# PROB_S7CAS_Connectors.net
KiCad netlist of a schematic drawn in Altium Designer
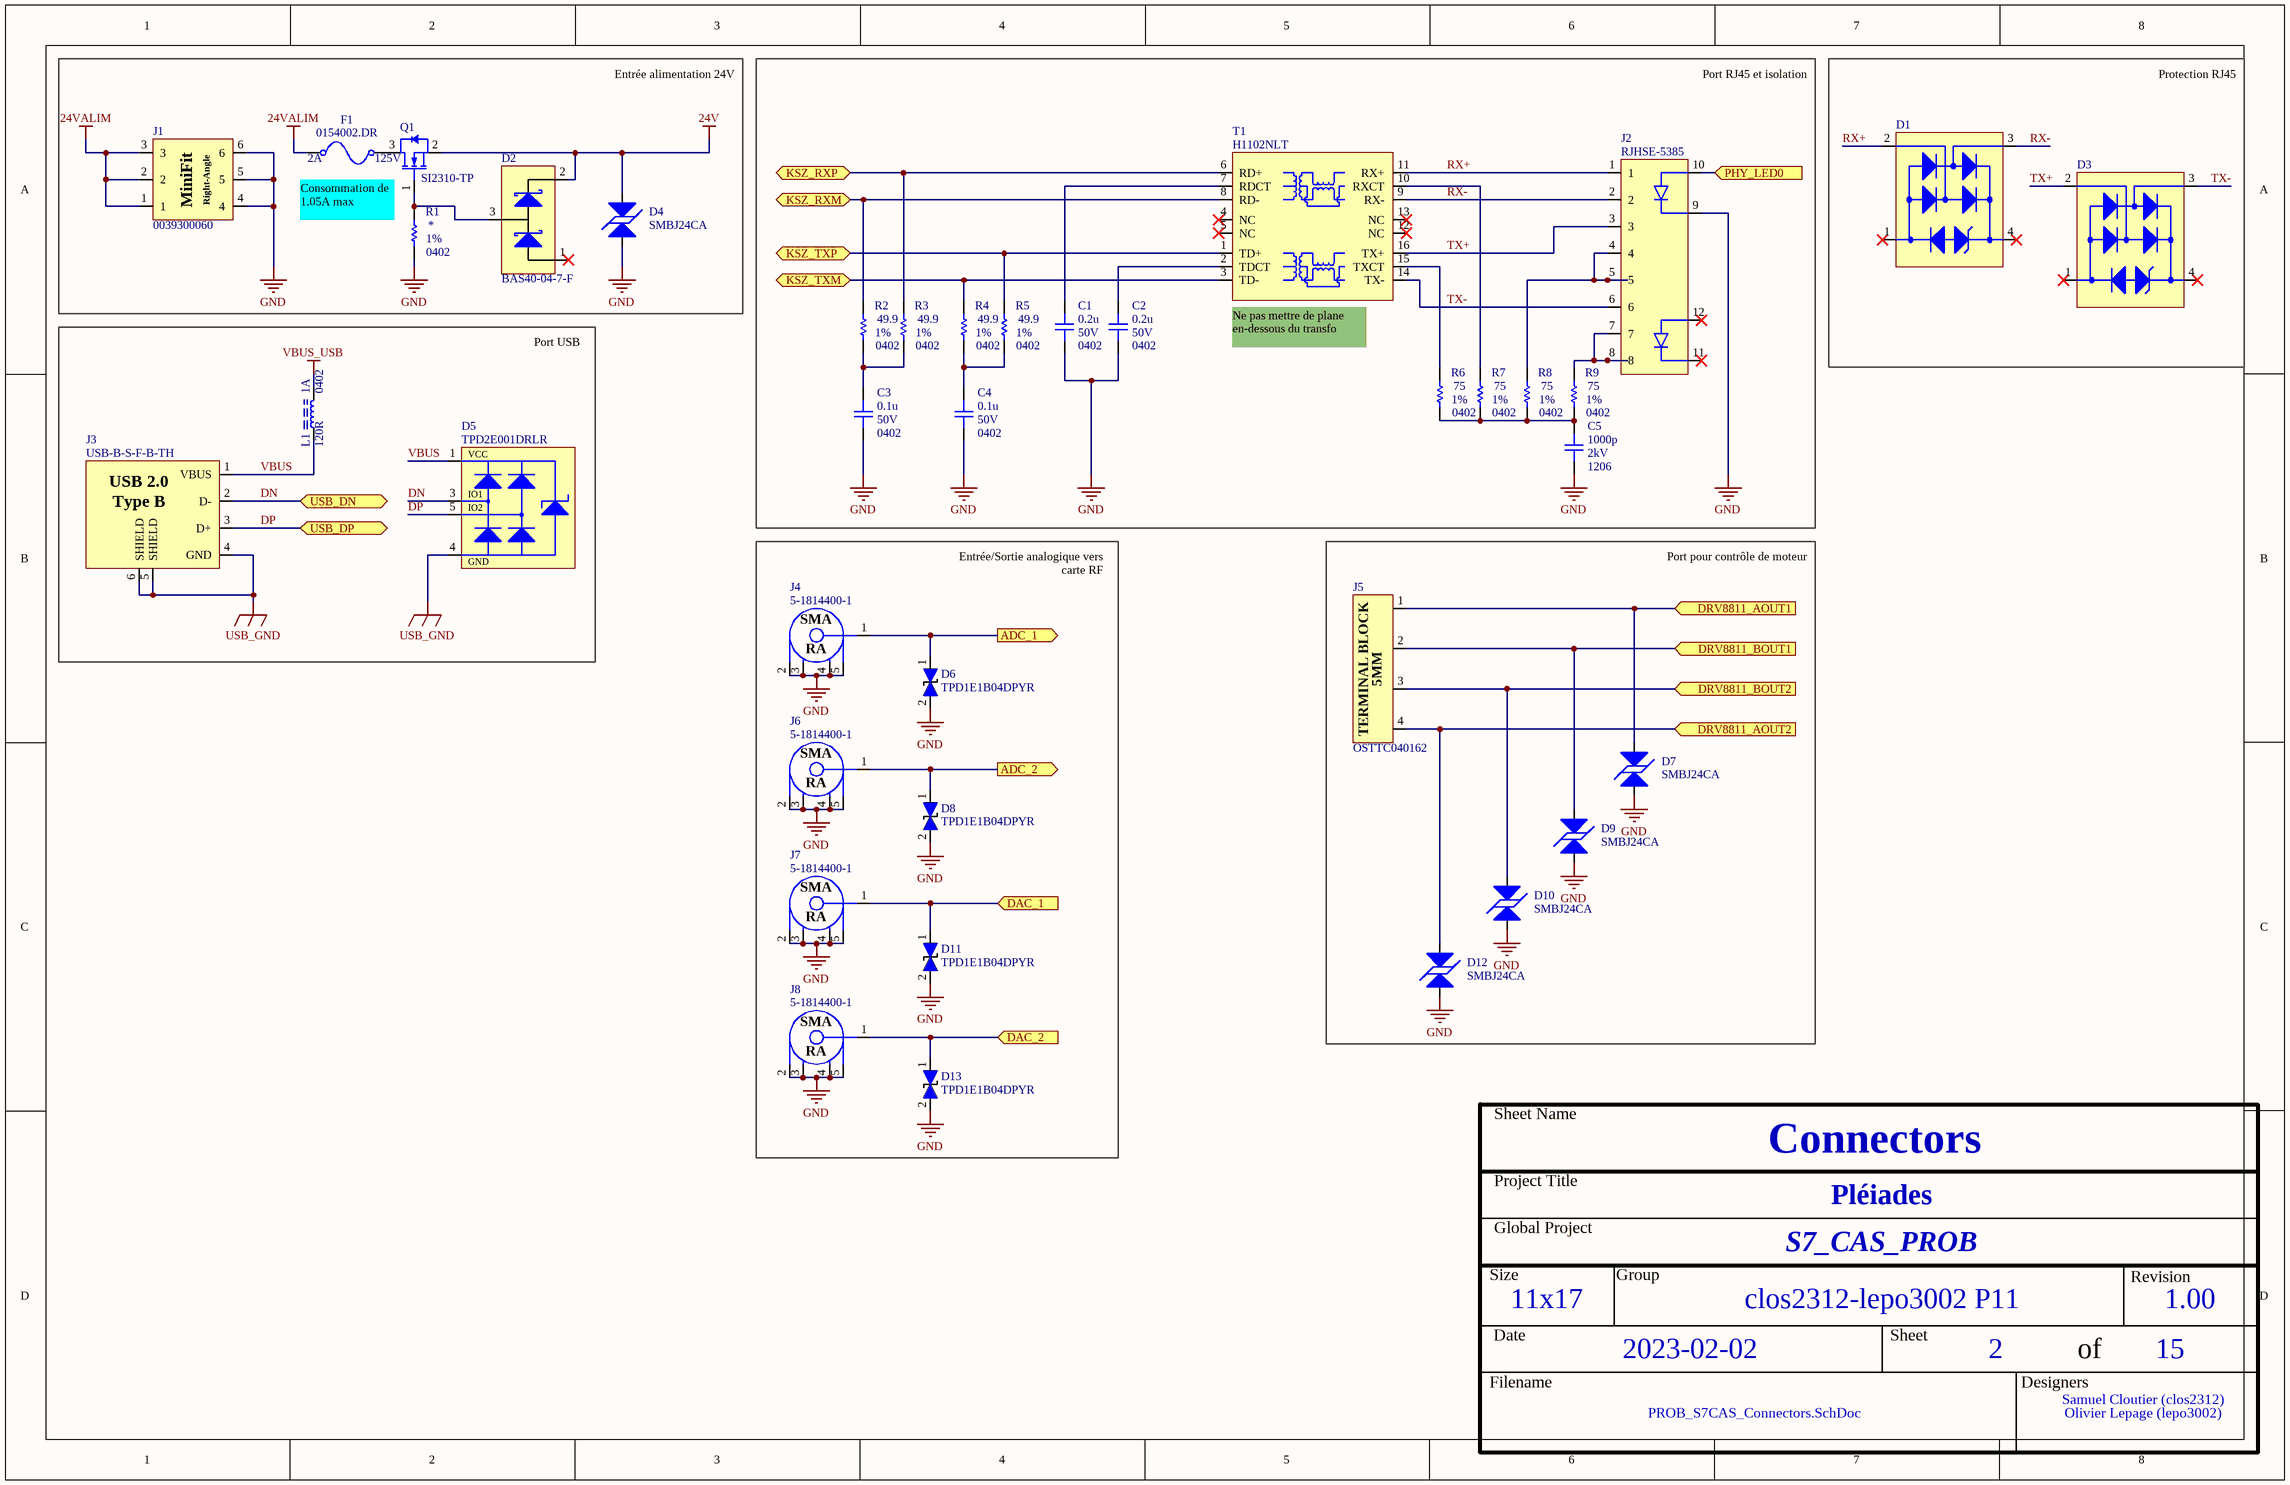
[diagram p0: PROB_S7CAS_Connectors.SchDoc]

(export (version "E")
  (design (tool "Eeschema 10.0.6"))
  (components
    (comp (ref "C1")
      (value "0.2u")
      (footprint "CAP_0402")
      (description "CAP - 0402")
      (fields
        (field (name "VOLTAGE") "50V")
        (field (name "PACKAGE") "0402")
        (field (name "CREATEDBY") "Jonathan Bouchard")
      )
      (libsource (lib "S7CAS_LIB2021") (part "CAP - 0402"))
    )
    (comp (ref "C2")
      (value "0.2u")
      (footprint "CAP_0402")
      (description "CAP - 0402")
      (fields
        (field (name "VOLTAGE") "50V")
        (field (name "PACKAGE") "0402")
        (field (name "CREATEDBY") "Jonathan Bouchard")
      )
      (libsource (lib "S7CAS_LIB2021") (part "CAP - 0402"))
    )
    (comp (ref "C3")
      (value "0.1u")
      (footprint "CAP_0402")
      (description "CAP - 0402")
      (fields
        (field (name "VOLTAGE") "50V")
        (field (name "PACKAGE") "0402")
        (field (name "CREATEDBY") "Jonathan Bouchard")
      )
      (libsource (lib "S7CAS_LIB2021") (part "CAP - 0402"))
    )
    (comp (ref "C4")
      (value "0.1u")
      (footprint "CAP_0402")
      (description "CAP - 0402")
      (fields
        (field (name "VOLTAGE") "50V")
        (field (name "PACKAGE") "0402")
        (field (name "CREATEDBY") "Jonathan Bouchard")
      )
      (libsource (lib "S7CAS_LIB2021") (part "CAP - 0402"))
    )
    (comp (ref "C5")
      (value "1000p")
      (footprint "CAP_0402")
      (description "CAP - 0402")
      (fields
        (field (name "VOLTAGE") "2kV")
        (field (name "PACKAGE") "1206")
        (field (name "CREATEDBY") "Jonathan Bouchard")
      )
      (libsource (lib "S7CAS_LIB2021") (part "CAP - 0402"))
    )
    (comp (ref "D1")
      (value "SR3.3.TCT")
      (footprint "TVS_SR3.3.TCT")
      (description "TVS - DIODE ARRAY 3.3V 150W - SOT143-4")
      (fields
        (field (name "MFG") "Semtech")
        (field (name "POWER") "150W")
        (field (name "CREATEDBY") "Jonathan Bouchard")
      )
      (libsource (lib "S7CAS_LIB2021") (part "TVS_SR3.3.TCT"))
    )
    (comp (ref "D2")
      (value "BAS40-04-7-F")
      (footprint "DIO_SCHOTTKY_BAS40-04-7-F")
      (description "DIO - Schottky Array 1 Pair Series Connection - SOT-23-3")
      (fields
        (field (name "CREATEDBY/DATE") "Danae D-F 15 août 2019")
        (field (name "VERIFIEDBY") "C.Paulin - 16/08/2019")
      )
      (libsource (lib "S7CAS_LIB2021") (part "DIO_SCHOTTKY_BAS40-04-7-F"))
    )
    (comp (ref "D3")
      (value "SR3.3.TCT")
      (footprint "TVS_SR3.3.TCT")
      (description "TVS - DIODE ARRAY 3.3V 150W - SOT143-4")
      (fields
        (field (name "MFG") "Semtech")
        (field (name "POWER") "150W")
        (field (name "CREATEDBY") "Jonathan Bouchard")
      )
      (libsource (lib "S7CAS_LIB2021") (part "TVS_SR3.3.TCT"))
    )
    (comp (ref "D4")
      (value "SMBJ24CA")
      (footprint "TVS_PWR_SMBJ36CA")
      (description "TVS - 24V 26.7V 600W - DO214AA")
      (fields
        (field (name "CREATEDBY/DATE") "Arnaud Samson - 06/07/18")
        (field (name "VERIFIEDBY") "Jonathan Bouchard - 2018-07-13")
      )
      (libsource (lib "S7CAS_LIB2021") (part "TVS_PWR_SMBJ24CA"))
    )
    (comp (ref "D5")
      (value "TPD2E001DRLR")
      (footprint "TVS_USB_TPD2E001DRLR")
      (description "TVS - USB TVS DIODE 5.5V - SOT-553")
      (fields
        (field (name "CREATEDBY/DATE") "Jonathan Bouchard 2018-07-10")
        (field (name "VERIFIEDBY") "Arnaud Samson 16-07-18")
      )
      (libsource (lib "S7CAS_LIB2021") (part "TVS_USB_TPD2E001DRLR"))
    )
    (comp (ref "D6")
      (value "TPD1E1B04DPYR")
      (footprint "TVS_DATA_TPD1E1B04DPYR")
      (description "TVS - TVS DIODE 3.6V 8.5V - 0402")
      (fields
        (field (name "CREATEDBY/DATE") "Keven Deslandes - 2018/10/19")
        (field (name "VERIFIEDBY") "Caroline Paulin - 28 janv 2019")
      )
      (libsource (lib "S7CAS_LIB2021") (part "TVS_DATA_TPD1E1B04DPYR"))
    )
    (comp (ref "D7")
      (value "SMBJ24CA")
      (footprint "TVS_PWR_SMBJ36CA")
      (description "TVS - 24V 26.7V 600W - DO214AA")
      (fields
        (field (name "CREATEDBY/DATE") "Arnaud Samson - 06/07/18")
        (field (name "VERIFIEDBY") "Jonathan Bouchard - 2018-07-13")
      )
      (libsource (lib "S7CAS_LIB2021") (part "TVS_PWR_SMBJ24CA"))
    )
    (comp (ref "D8")
      (value "TPD1E1B04DPYR")
      (footprint "TVS_DATA_TPD1E1B04DPYR")
      (description "TVS - TVS DIODE 3.6V 8.5V - 0402")
      (fields
        (field (name "CREATEDBY/DATE") "Keven Deslandes - 2018/10/19")
        (field (name "VERIFIEDBY") "Caroline Paulin - 28 janv 2019")
      )
      (libsource (lib "S7CAS_LIB2021") (part "TVS_DATA_TPD1E1B04DPYR"))
    )
    (comp (ref "D9")
      (value "SMBJ24CA")
      (footprint "TVS_PWR_SMBJ36CA")
      (description "TVS - 24V 26.7V 600W - DO214AA")
      (fields
        (field (name "CREATEDBY/DATE") "Arnaud Samson - 06/07/18")
        (field (name "VERIFIEDBY") "Jonathan Bouchard - 2018-07-13")
      )
      (libsource (lib "S7CAS_LIB2021") (part "TVS_PWR_SMBJ24CA"))
    )
    (comp (ref "D10")
      (value "SMBJ24CA")
      (footprint "TVS_PWR_SMBJ36CA")
      (description "TVS - 24V 26.7V 600W - DO214AA")
      (fields
        (field (name "CREATEDBY/DATE") "Arnaud Samson - 06/07/18")
        (field (name "VERIFIEDBY") "Jonathan Bouchard - 2018-07-13")
      )
      (libsource (lib "S7CAS_LIB2021") (part "TVS_PWR_SMBJ24CA"))
    )
    (comp (ref "D11")
      (value "TPD1E1B04DPYR")
      (footprint "TVS_DATA_TPD1E1B04DPYR")
      (description "TVS - TVS DIODE 3.6V 8.5V - 0402")
      (fields
        (field (name "CREATEDBY/DATE") "Keven Deslandes - 2018/10/19")
        (field (name "VERIFIEDBY") "Caroline Paulin - 28 janv 2019")
      )
      (libsource (lib "S7CAS_LIB2021") (part "TVS_DATA_TPD1E1B04DPYR"))
    )
    (comp (ref "D12")
      (value "SMBJ24CA")
      (footprint "TVS_PWR_SMBJ36CA")
      (description "TVS - 24V 26.7V 600W - DO214AA")
      (fields
        (field (name "CREATEDBY/DATE") "Arnaud Samson - 06/07/18")
        (field (name "VERIFIEDBY") "Jonathan Bouchard - 2018-07-13")
      )
      (libsource (lib "S7CAS_LIB2021") (part "TVS_PWR_SMBJ24CA"))
    )
    (comp (ref "D13")
      (value "TPD1E1B04DPYR")
      (footprint "TVS_DATA_TPD1E1B04DPYR")
      (description "TVS - TVS DIODE 3.6V 8.5V - 0402")
      (fields
        (field (name "CREATEDBY/DATE") "Keven Deslandes - 2018/10/19")
        (field (name "VERIFIEDBY") "Caroline Paulin - 28 janv 2019")
      )
      (libsource (lib "S7CAS_LIB2021") (part "TVS_DATA_TPD1E1B04DPYR"))
    )
    (comp (ref "F1")
      (value "0154002.DR")
      (footprint "FUS_0154XXX.DR")
      (description "FUS - 2 A 125 VAC/VDC - 2-SMD")
      (fields
        (field (name "VOLTAGE RATING") "125V")
        (field (name "CURRENT RATING") "2A")
        (field (name "CREATEDBY/DATE") "Jonathan Bouchard 2018-07-17")
        (field (name "VERIFIEDBY") "Arnaud Samson 23-07-18")
      )
      (libsource (lib "S7CAS_LIB2021") (part "FUS_0154002.DR"))
    )
    (comp (ref "J1")
      (value "0039300060")
      (footprint "CON_MINIFIT_0039300060")
      (description "CON - Mini-Fit Through Hole, Right Angle 6 position")
      (fields
        (field (name "CREATEDBY/DATE") "Joel Lemay 2018-06-21")
        (field (name "VERIFIEDBY") "Caroline Paulin - 10 sept 2018")
      )
      (libsource (lib "S7CAS_LIB2021") (part "CON_MINIFIT_0039300060"))
    )
    (comp (ref "J2")
      (value "RJHSE-5385")
      (footprint "CONN_ETHERNET_RJHSE-5385")
      (description "CONN - MOD JACK RJ45 R/A ETHERNET - TH")
      (fields (field (name "MFG") "Amphenol") (field (name "CREATEDBY") "Jonathan Bouchard"))
      (libsource (lib "S7CAS_LIB2021") (part "CONN_ETHERNET_RJHSE-5385"))
    )
    (comp (ref "J3")
      (value "USB-B-S-F-B-TH")
      (footprint "CON_USB_USB-B-S-F-B-TH")
      (description "CON - USB B RECPT TH R/A - 4-TH")
      (fields
        (field (name "CREATEDBY/DATE") "Jonathan Bouchard 2020-03-24")
        (field (name "VERIFIEDBY") "C.Paulin - 22/04/2020")
      )
      (libsource (lib "S7CAS_LIB2021") (part "CON_USB_USB-B-S-F-B-TH"))
    )
    (comp (ref "J4")
      (value "5-1814400-1")
      (footprint "CONN_SMA_5-1814400-1")
      (description "CONN -  SMA JACK R/A 50 OHM - TH")
      (fields
        (field (name "MFG") "TE Connectivity AMP Connectors")
        (field (name "CREATEDBY") "Jonathan Bouchard")
      )
      (libsource (lib "S7CAS_LIB2021") (part "CONN_SMA_5-1814400-1"))
    )
    (comp (ref "J5")
      (value "OSTTC040162")
      (footprint "CONN_TERMINAL_OSTTA040161")
      (description "CONN -  TERMINAL BLOCK 4POS 5MM - TH")
      (fields (field (name "MFG") "On Shore Technology Inc.") (field (name "CREATEDBY") "Jonathan Bouchard"))
      (libsource (lib "S7CAS_LIB2021") (part "CONN_TERMINAL_OSTTC040162"))
    )
    (comp (ref "J6")
      (value "5-1814400-1")
      (footprint "CONN_SMA_5-1814400-1")
      (description "CONN -  SMA JACK R/A 50 OHM - TH")
      (fields
        (field (name "MFG") "TE Connectivity AMP Connectors")
        (field (name "CREATEDBY") "Jonathan Bouchard")
      )
      (libsource (lib "S7CAS_LIB2021") (part "CONN_SMA_5-1814400-1"))
    )
    (comp (ref "J7")
      (value "5-1814400-1")
      (footprint "CONN_SMA_5-1814400-1")
      (description "CONN -  SMA JACK R/A 50 OHM - TH")
      (fields
        (field (name "MFG") "TE Connectivity AMP Connectors")
        (field (name "CREATEDBY") "Jonathan Bouchard")
      )
      (libsource (lib "S7CAS_LIB2021") (part "CONN_SMA_5-1814400-1"))
    )
    (comp (ref "J8")
      (value "5-1814400-1")
      (footprint "CONN_SMA_5-1814400-1")
      (description "CONN -  SMA JACK R/A 50 OHM - TH")
      (fields
        (field (name "MFG") "TE Connectivity AMP Connectors")
        (field (name "CREATEDBY") "Jonathan Bouchard")
      )
      (libsource (lib "S7CAS_LIB2021") (part "CONN_SMA_5-1814400-1"))
    )
    (comp (ref "L1")
      (value "120R")
      (footprint "FER_0402")
      (description "FER - 0402")
      (fields
        (field (name "CURRENT") "1A")
        (field (name "PACKAGE") "0402")
        (field (name "CREATEDBY") "Jonathan Bouchard")
      )
      (libsource (lib "S7CAS_LIB2021") (part "FER - 0402"))
    )
    (comp (ref "Q1")
      (value "SI2310-TP")
      (footprint "TRX_NMOS_SI2310-TP")
      (description "TRX - MOSFET N-CH 60V 3A - SOT-23")
      (fields
        (field (name "CREATEDBY/DATE") "Louis-Daniel Gaulin / 20-02-2020")
        (field (name "VERIFIEDBY") "C.Paulin - 21/02/2020")
      )
      (libsource (lib "S7CAS_LIB2021") (part "TRX_NMOS_SI2310-TP"))
    )
    (comp (ref "R1")
      (value "RES - 0402")
      (footprint "RES_0402")
      (fields
        (field (name "VOLTAGE") "50V")
        (field (name "POWER") "1/16W")
        (field (name "PACKAGE") "0402")
        (field (name "PRECISION") "1%")
        (field (name "ALTIUM_VALUE") "*")
        (field (name "CREATEDBY") "Jonathan Bouchard")
      )
      (libsource (lib "S7CAS_LIB2021") (part "RES - 0402"))
    )
    (comp (ref "R2")
      (value "49.9")
      (footprint "RES_0402")
      (description "RES - 0402")
      (fields
        (field (name "VOLTAGE") "50V")
        (field (name "POWER") "1/16W")
        (field (name "PACKAGE") "0402")
        (field (name "PRECISION") "1%")
        (field (name "CREATEDBY") "Jonathan Bouchard")
      )
      (libsource (lib "S7CAS_LIB2021") (part "RES - 0402"))
    )
    (comp (ref "R3")
      (value "49.9")
      (footprint "RES_0402")
      (description "RES - 0402")
      (fields
        (field (name "VOLTAGE") "50V")
        (field (name "POWER") "1/16W")
        (field (name "PACKAGE") "0402")
        (field (name "PRECISION") "1%")
        (field (name "CREATEDBY") "Jonathan Bouchard")
      )
      (libsource (lib "S7CAS_LIB2021") (part "RES - 0402"))
    )
    (comp (ref "R4")
      (value "49.9")
      (footprint "RES_0402")
      (description "RES - 0402")
      (fields
        (field (name "VOLTAGE") "50V")
        (field (name "POWER") "1/16W")
        (field (name "PACKAGE") "0402")
        (field (name "PRECISION") "1%")
        (field (name "CREATEDBY") "Jonathan Bouchard")
      )
      (libsource (lib "S7CAS_LIB2021") (part "RES - 0402"))
    )
    (comp (ref "R5")
      (value "49.9")
      (footprint "RES_0402")
      (description "RES - 0402")
      (fields
        (field (name "VOLTAGE") "50V")
        (field (name "POWER") "1/16W")
        (field (name "PACKAGE") "0402")
        (field (name "PRECISION") "1%")
        (field (name "CREATEDBY") "Jonathan Bouchard")
      )
      (libsource (lib "S7CAS_LIB2021") (part "RES - 0402"))
    )
    (comp (ref "R6")
      (value "75")
      (footprint "RES_0402")
      (description "RES - 0402")
      (fields
        (field (name "VOLTAGE") "50V")
        (field (name "POWER") "1/16W")
        (field (name "PACKAGE") "0402")
        (field (name "PRECISION") "1%")
        (field (name "CREATEDBY") "Jonathan Bouchard")
      )
      (libsource (lib "S7CAS_LIB2021") (part "RES - 0402"))
    )
    (comp (ref "R7")
      (value "75")
      (footprint "RES_0402")
      (description "RES - 0402")
      (fields
        (field (name "VOLTAGE") "50V")
        (field (name "POWER") "1/16W")
        (field (name "PACKAGE") "0402")
        (field (name "PRECISION") "1%")
        (field (name "CREATEDBY") "Jonathan Bouchard")
      )
      (libsource (lib "S7CAS_LIB2021") (part "RES - 0402"))
    )
    (comp (ref "R8")
      (value "75")
      (footprint "RES_0402")
      (description "RES - 0402")
      (fields
        (field (name "VOLTAGE") "50V")
        (field (name "POWER") "1/16W")
        (field (name "PACKAGE") "0402")
        (field (name "PRECISION") "1%")
        (field (name "CREATEDBY") "Jonathan Bouchard")
      )
      (libsource (lib "S7CAS_LIB2021") (part "RES - 0402"))
    )
    (comp (ref "R9")
      (value "75")
      (footprint "RES_0402")
      (description "RES - 0402")
      (fields
        (field (name "VOLTAGE") "50V")
        (field (name "POWER") "1/16W")
        (field (name "PACKAGE") "0402")
        (field (name "PRECISION") "1%")
        (field (name "CREATEDBY") "Jonathan Bouchard")
      )
      (libsource (lib "S7CAS_LIB2021") (part "RES - 0402"))
    )
    (comp (ref "T1")
      (value "H1102NLT")
      (footprint "TRANSFO_H1102NLT")
      (description "TRANSFO - ETHERNET 10/100B-TX - SMD-16")
      (fields (field (name "MFG") "Pulse Eng.") (field (name "CREATEDBY") "Jonathan Bouchard"))
      (libsource (lib "S7CAS_LIB2021") (part "TRANSFO_H1102NLT"))
    )
  )
  (nets
    (net (code "1") (name "/ADC_1") (class "Default")
      (node (ref "D6") (pin "1") (pinfunction "i/o_1") (pintype "passive"))
      (node (ref "J4") (pin "1") (pinfunction "1_1") (pintype "passive"))
    )
    (net (code "2") (name "/ADC_2") (class "Default")
      (node (ref "D8") (pin "1") (pinfunction "i/o_1") (pintype "passive"))
      (node (ref "J6") (pin "1") (pinfunction "1_1") (pintype "passive"))
    )
    (net (code "3") (name "/DAC_1") (class "Default")
      (node (ref "D11") (pin "1") (pinfunction "i/o_1") (pintype "passive"))
      (node (ref "J7") (pin "1") (pinfunction "1_1") (pintype "passive"))
    )
    (net (code "4") (name "/DAC_2") (class "Default")
      (node (ref "D13") (pin "1") (pinfunction "i/o_1") (pintype "passive"))
      (node (ref "J8") (pin "1") (pinfunction "1_1") (pintype "passive"))
    )
    (net (code "5") (name "/DN") (class "Default")
      (node (ref "D5") (pin "3") (pinfunction "IO1_3") (pintype "passive"))
      (node (ref "J3") (pin "2") (pinfunction "D-_2") (pintype "passive"))
    )
    (net (code "6") (name "/DP") (class "Default")
      (node (ref "D5") (pin "5") (pinfunction "IO2_5") (pintype "passive"))
      (node (ref "J3") (pin "3") (pinfunction "D+_3") (pintype "passive"))
    )
    (net (code "7") (name "/DRV8811_AOUT1") (class "Default")
      (node (ref "D7") (pin "1") (pinfunction "1_1") (pintype "passive"))
      (node (ref "J5") (pin "1") (pinfunction "1_1") (pintype "passive"))
    )
    (net (code "8") (name "/DRV8811_AOUT2") (class "Default")
      (node (ref "D12") (pin "1") (pinfunction "1_1") (pintype "passive"))
      (node (ref "J5") (pin "4") (pinfunction "4_4") (pintype "passive"))
    )
    (net (code "9") (name "/DRV8811_BOUT1") (class "Default")
      (node (ref "D9") (pin "1") (pinfunction "1_1") (pintype "passive"))
      (node (ref "J5") (pin "2") (pinfunction "2_2") (pintype "passive"))
    )
    (net (code "10") (name "/DRV8811_BOUT2") (class "Default")
      (node (ref "D10") (pin "1") (pinfunction "1_1") (pintype "passive"))
      (node (ref "J5") (pin "3") (pinfunction "3_3") (pintype "passive"))
    )
    (net (code "11") (name "/KSZ_RXM") (class "Default")
      (node (ref "R2") (pin "2") (pinfunction "2_2") (pintype "passive"))
      (node (ref "T1") (pin "8") (pinfunction "RD-_8") (pintype "passive"))
    )
    (net (code "12") (name "/KSZ_RXP") (class "Default")
      (node (ref "R3") (pin "2") (pinfunction "2_2") (pintype "passive"))
      (node (ref "T1") (pin "6") (pinfunction "RD+_6") (pintype "passive"))
    )
    (net (code "13") (name "/KSZ_TXM") (class "Default")
      (node (ref "R4") (pin "2") (pinfunction "2_2") (pintype "passive"))
      (node (ref "T1") (pin "3") (pinfunction "TD-_3") (pintype "passive"))
    )
    (net (code "14") (name "/KSZ_TXP") (class "Default")
      (node (ref "R5") (pin "2") (pinfunction "2_2") (pintype "passive"))
      (node (ref "T1") (pin "1") (pinfunction "TD+_1") (pintype "passive"))
    )
    (net (code "15") (name "/PHY_LED0") (class "Default")
      (node (ref "J2") (pin "10") (pinfunction "LED1_A_10") (pintype "passive"))
    )
    (net (code "16") (name "/RX+") (class "Default")
      (node (ref "D1") (pin "2") (pinfunction "VN_2") (pintype "passive"))
      (node (ref "J2") (pin "1") (pinfunction "1_1") (pintype "passive"))
      (node (ref "T1") (pin "11") (pinfunction "RX+_11") (pintype "passive"))
    )
    (net (code "17") (name "/RX-") (class "Default")
      (node (ref "D1") (pin "3") (pintype "passive"))
      (node (ref "J2") (pin "2") (pinfunction "2_2") (pintype "passive"))
      (node (ref "T1") (pin "9") (pinfunction "RX-_9") (pintype "passive"))
    )
    (net (code "18") (name "/TX+") (class "Default")
      (node (ref "D3") (pin "2") (pinfunction "VN_2") (pintype "passive"))
      (node (ref "J2") (pin "3") (pinfunction "3_3") (pintype "passive"))
      (node (ref "T1") (pin "16") (pinfunction "TX+_16") (pintype "passive"))
    )
    (net (code "19") (name "/TX-") (class "Default")
      (node (ref "D3") (pin "3") (pintype "passive"))
      (node (ref "J2") (pin "6") (pinfunction "6_6") (pintype "passive"))
      (node (ref "T1") (pin "14") (pinfunction "TX-_14") (pintype "passive"))
    )
    (net (code "20") (name "/VBUS") (class "Default")
      (node (ref "D5") (pin "1") (pinfunction "VCC_1") (pintype "passive"))
      (node (ref "J3") (pin "1") (pinfunction "VBUS_1") (pintype "passive"))
      (node (ref "L1") (pin "2") (pinfunction "2_2") (pintype "passive"))
    )
    (net (code "21") (name "24V") (class "Default")
      (node (ref "D2") (pin "2") (pinfunction "K_2") (pintype "passive"))
      (node (ref "D4") (pin "1") (pinfunction "1_1") (pintype "passive"))
      (node (ref "Q1") (pin "2") (pinfunction "S_2") (pintype "passive"))
    )
    (net (code "22") (name "24VALIM") (class "Default")
      (node (ref "F1") (pin "1") (pinfunction "1_1") (pintype "passive"))
      (node (ref "J1") (pin "1") (pinfunction "1_1") (pintype "passive"))
      (node (ref "J1") (pin "2") (pinfunction "2_2") (pintype "passive"))
      (node (ref "J1") (pin "3") (pinfunction "3_3") (pintype "passive"))
    )
    (net (code "23") (name "GND") (class "Default")
      (node (ref "C1") (pin "1") (pinfunction "1_1") (pintype "passive"))
      (node (ref "C2") (pin "1") (pinfunction "1_1") (pintype "passive"))
      (node (ref "C3") (pin "1") (pinfunction "1_1") (pintype "passive"))
      (node (ref "C4") (pin "1") (pinfunction "1_1") (pintype "passive"))
      (node (ref "C5") (pin "1") (pinfunction "1_1") (pintype "passive"))
      (node (ref "D10") (pin "2") (pinfunction "2_2") (pintype "passive"))
      (node (ref "D11") (pin "2") (pinfunction "i/o_2") (pintype "passive"))
      (node (ref "D12") (pin "2") (pinfunction "2_2") (pintype "passive"))
      (node (ref "D13") (pin "2") (pinfunction "i/o_2") (pintype "passive"))
      (node (ref "D4") (pin "2") (pinfunction "2_2") (pintype "passive"))
      (node (ref "D6") (pin "2") (pinfunction "i/o_2") (pintype "passive"))
      (node (ref "D7") (pin "2") (pinfunction "2_2") (pintype "passive"))
      (node (ref "D8") (pin "2") (pinfunction "i/o_2") (pintype "passive"))
      (node (ref "D9") (pin "2") (pinfunction "2_2") (pintype "passive"))
      (node (ref "J1") (pin "4") (pinfunction "4_4") (pintype "passive"))
      (node (ref "J1") (pin "5") (pinfunction "5_5") (pintype "passive"))
      (node (ref "J1") (pin "6") (pinfunction "6_6") (pintype "passive"))
      (node (ref "J2") (pin "9") (pinfunction "LED1_K_9") (pintype "passive"))
      (node (ref "J4") (pin "2") (pinfunction "2_2") (pintype "passive"))
      (node (ref "J4") (pin "3") (pinfunction "3_3") (pintype "passive"))
      (node (ref "J4") (pin "4") (pinfunction "4_4") (pintype "passive"))
      (node (ref "J4") (pin "5") (pinfunction "5_5") (pintype "passive"))
      (node (ref "J6") (pin "2") (pinfunction "2_2") (pintype "passive"))
      (node (ref "J6") (pin "3") (pinfunction "3_3") (pintype "passive"))
      (node (ref "J6") (pin "4") (pinfunction "4_4") (pintype "passive"))
      (node (ref "J6") (pin "5") (pinfunction "5_5") (pintype "passive"))
      (node (ref "J7") (pin "2") (pinfunction "2_2") (pintype "passive"))
      (node (ref "J7") (pin "3") (pinfunction "3_3") (pintype "passive"))
      (node (ref "J7") (pin "4") (pinfunction "4_4") (pintype "passive"))
      (node (ref "J7") (pin "5") (pinfunction "5_5") (pintype "passive"))
      (node (ref "J8") (pin "2") (pinfunction "2_2") (pintype "passive"))
      (node (ref "J8") (pin "3") (pinfunction "3_3") (pintype "passive"))
      (node (ref "J8") (pin "4") (pinfunction "4_4") (pintype "passive"))
      (node (ref "J8") (pin "5") (pinfunction "5_5") (pintype "passive"))
      (node (ref "R1") (pin "1") (pinfunction "1_1") (pintype "passive"))
    )
    (net (code "24") (name "Net-(C3-Pad2)") (class "Default")
      (node (ref "C3") (pin "2") (pinfunction "2_2") (pintype "passive"))
      (node (ref "R2") (pin "1") (pinfunction "1_1") (pintype "passive"))
      (node (ref "R3") (pin "1") (pinfunction "1_1") (pintype "passive"))
    )
    (net (code "25") (name "Net-(C4-Pad2)") (class "Default")
      (node (ref "C4") (pin "2") (pinfunction "2_2") (pintype "passive"))
      (node (ref "R4") (pin "1") (pinfunction "1_1") (pintype "passive"))
      (node (ref "R5") (pin "1") (pinfunction "1_1") (pintype "passive"))
    )
    (net (code "26") (name "Net-(C5-Pad2)") (class "Default")
      (node (ref "C5") (pin "2") (pinfunction "2_2") (pintype "passive"))
      (node (ref "R6") (pin "1") (pinfunction "1_1") (pintype "passive"))
      (node (ref "R7") (pin "1") (pinfunction "1_1") (pintype "passive"))
      (node (ref "R8") (pin "1") (pinfunction "1_1") (pintype "passive"))
      (node (ref "R9") (pin "1") (pinfunction "1_1") (pintype "passive"))
    )
    (net (code "27") (name "Net-(D2-AK)") (class "Default")
      (node (ref "D2") (pin "3") (pinfunction "AK_3") (pintype "passive"))
      (node (ref "Q1") (pin "1") (pinfunction "G_1") (pintype "passive"))
      (node (ref "R1") (pin "2") (pinfunction "2_2") (pintype "passive"))
    )
    (net (code "28") (name "Net-(J2-Pad4)") (class "Default")
      (node (ref "J2") (pin "4") (pinfunction "4_4") (pintype "passive"))
      (node (ref "J2") (pin "5") (pinfunction "5_5") (pintype "passive"))
      (node (ref "R8") (pin "2") (pinfunction "2_2") (pintype "passive"))
    )
    (net (code "29") (name "Net-(J2-Pad7)") (class "Default")
      (node (ref "J2") (pin "7") (pinfunction "7_7") (pintype "passive"))
      (node (ref "J2") (pin "8") (pinfunction "8_8") (pintype "passive"))
      (node (ref "R9") (pin "2") (pinfunction "2_2") (pintype "passive"))
    )
    (net (code "30") (name "Net-(Q1-D)") (class "Default")
      (node (ref "F1") (pin "2") (pinfunction "2_2") (pintype "passive"))
      (node (ref "Q1") (pin "3") (pinfunction "D_3") (pintype "passive"))
    )
    (net (code "31") (name "Net-(T1-RDCT)") (class "Default")
      (node (ref "C1") (pin "2") (pinfunction "2_2") (pintype "passive"))
      (node (ref "T1") (pin "7") (pinfunction "RDCT_7") (pintype "passive"))
    )
    (net (code "32") (name "Net-(T1-RXCT)") (class "Default")
      (node (ref "R7") (pin "2") (pinfunction "2_2") (pintype "passive"))
      (node (ref "T1") (pin "10") (pinfunction "RXCT_10") (pintype "passive"))
    )
    (net (code "33") (name "Net-(T1-TDCT)") (class "Default")
      (node (ref "C2") (pin "2") (pinfunction "2_2") (pintype "passive"))
      (node (ref "T1") (pin "2") (pinfunction "TDCT_2") (pintype "passive"))
    )
    (net (code "34") (name "Net-(T1-TXCT)") (class "Default")
      (node (ref "R6") (pin "2") (pinfunction "2_2") (pintype "passive"))
      (node (ref "T1") (pin "15") (pinfunction "TXCT_15") (pintype "passive"))
    )
    (net (code "35") (name "USB_GND") (class "Default")
      (node (ref "D5") (pin "4") (pinfunction "GND_4") (pintype "passive"))
      (node (ref "J3") (pin "4") (pinfunction "GND_4") (pintype "passive"))
      (node (ref "J3") (pin "5") (pinfunction "SHIELD_5") (pintype "passive"))
      (node (ref "J3") (pin "6") (pinfunction "SHIELD_6") (pintype "passive"))
    )
    (net (code "36") (name "VBUS_USB") (class "Default")
      (node (ref "L1") (pin "1") (pinfunction "1_1") (pintype "passive"))
    )
    (net (code "37") (name "unconnected-(D1-I{slash}O-Pad1)") (class "Default")
      (node (ref "D1") (pin "1") (pinfunction "I/O_1") (pintype "passive+no_connect"))
    )
    (net (code "38") (name "unconnected-(D1-Pad4)") (class "Default")
      (node (ref "D1") (pin "4") (pintype "passive+no_connect"))
    )
    (net (code "39") (name "unconnected-(D2-A-Pad1)") (class "Default")
      (node (ref "D2") (pin "1") (pinfunction "A_1") (pintype "passive+no_connect"))
    )
    (net (code "40") (name "unconnected-(D3-I{slash}O-Pad1)") (class "Default")
      (node (ref "D3") (pin "1") (pinfunction "I/O_1") (pintype "passive+no_connect"))
    )
    (net (code "41") (name "unconnected-(D3-Pad4)") (class "Default")
      (node (ref "D3") (pin "4") (pintype "passive+no_connect"))
    )
    (net (code "42") (name "unconnected-(D5-NC-Pad2)") (class "Default")
      (node (ref "D5") (pin "2") (pinfunction "NC_2") (pintype "passive"))
    )
    (net (code "43") (name "unconnected-(J2-LED2_A-Pad12)") (class "Default")
      (node (ref "J2") (pin "12") (pinfunction "LED2_A_12") (pintype "passive+no_connect"))
    )
    (net (code "44") (name "unconnected-(J2-LED2_K-Pad11)") (class "Default")
      (node (ref "J2") (pin "11") (pinfunction "LED2_K_11") (pintype "passive+no_connect"))
    )
    (net (code "45") (name "unconnected-(T1-NC-Pad4)") (class "Default")
      (node (ref "T1") (pin "4") (pinfunction "NC_4") (pintype "passive+no_connect"))
    )
    (net (code "46") (name "unconnected-(T1-NC-Pad5)") (class "Default")
      (node (ref "T1") (pin "5") (pinfunction "NC_5") (pintype "passive+no_connect"))
    )
    (net (code "47") (name "unconnected-(T1-NC-Pad12)") (class "Default")
      (node (ref "T1") (pin "12") (pinfunction "NC_12") (pintype "passive+no_connect"))
    )
    (net (code "48") (name "unconnected-(T1-NC-Pad13)") (class "Default")
      (node (ref "T1") (pin "13") (pinfunction "NC_13") (pintype "passive+no_connect"))
    )
  )
)
